# Sheet1.net
KiCad netlist of a schematic drawn in Altium Designer
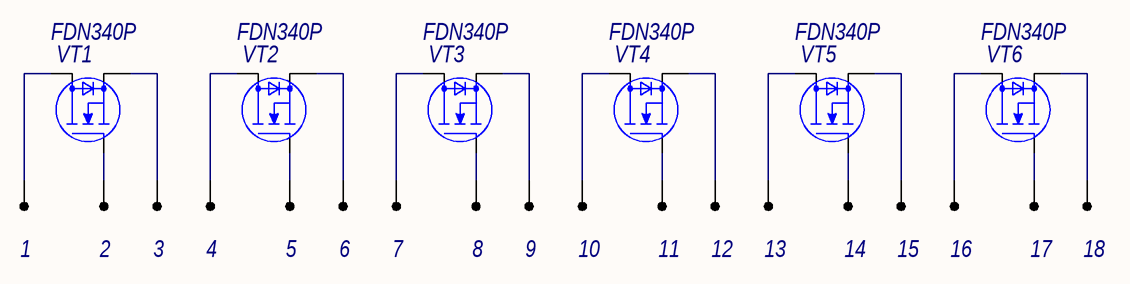
[diagram p0: Sheet1.SchDoc]

(export (version "E")
  (design (tool "Eeschema 10.0.6"))
  (components
    (comp (ref "1")
      (value "~")
      (footprint "WIRE_SOLDER_POINT2.1_0.5")
      (description "Контакт")
      (libsource (lib "headers") (part "SolderPoint"))
    )
    (comp (ref "2")
      (value "~")
      (footprint "WIRE_SOLDER_POINT2.1_0.5")
      (description "Контакт")
      (libsource (lib "headers") (part "SolderPoint"))
    )
    (comp (ref "3")
      (value "~")
      (footprint "WIRE_SOLDER_POINT2.1_0.5")
      (description "Контакт")
      (libsource (lib "headers") (part "SolderPoint"))
    )
    (comp (ref "4")
      (value "~")
      (footprint "WIRE_SOLDER_POINT2.1_0.5")
      (description "Контакт")
      (libsource (lib "headers") (part "SolderPoint"))
    )
    (comp (ref "5")
      (value "~")
      (footprint "WIRE_SOLDER_POINT2.1_0.5")
      (description "Контакт")
      (libsource (lib "headers") (part "SolderPoint"))
    )
    (comp (ref "6")
      (value "~")
      (footprint "WIRE_SOLDER_POINT2.1_0.5")
      (description "Контакт")
      (libsource (lib "headers") (part "SolderPoint"))
    )
    (comp (ref "7")
      (value "~")
      (footprint "WIRE_SOLDER_POINT2.1_0.5")
      (description "Контакт")
      (libsource (lib "headers") (part "SolderPoint"))
    )
    (comp (ref "8")
      (value "~")
      (footprint "WIRE_SOLDER_POINT2.1_0.5")
      (description "Контакт")
      (libsource (lib "headers") (part "SolderPoint"))
    )
    (comp (ref "9")
      (value "~")
      (footprint "WIRE_SOLDER_POINT2.1_0.5")
      (description "Контакт")
      (libsource (lib "headers") (part "SolderPoint"))
    )
    (comp (ref "10")
      (value "~")
      (footprint "WIRE_SOLDER_POINT2.1_0.5")
      (description "Контакт")
      (libsource (lib "headers") (part "SolderPoint"))
    )
    (comp (ref "11")
      (value "~")
      (footprint "WIRE_SOLDER_POINT2.1_0.5")
      (description "Контакт")
      (libsource (lib "headers") (part "SolderPoint"))
    )
    (comp (ref "12")
      (value "~")
      (footprint "WIRE_SOLDER_POINT2.1_0.5")
      (description "Контакт")
      (libsource (lib "headers") (part "SolderPoint"))
    )
    (comp (ref "13")
      (value "~")
      (footprint "WIRE_SOLDER_POINT2.1_0.5")
      (description "Контакт")
      (libsource (lib "headers") (part "SolderPoint"))
    )
    (comp (ref "14")
      (value "~")
      (footprint "WIRE_SOLDER_POINT2.1_0.5")
      (description "Контакт")
      (libsource (lib "headers") (part "SolderPoint"))
    )
    (comp (ref "15")
      (value "~")
      (footprint "WIRE_SOLDER_POINT2.1_0.5")
      (description "Контакт")
      (libsource (lib "headers") (part "SolderPoint"))
    )
    (comp (ref "16")
      (value "~")
      (footprint "WIRE_SOLDER_POINT2.1_0.5")
      (description "Контакт")
      (libsource (lib "headers") (part "SolderPoint"))
    )
    (comp (ref "17")
      (value "~")
      (footprint "WIRE_SOLDER_POINT2.1_0.5")
      (description "Контакт")
      (libsource (lib "headers") (part "SolderPoint"))
    )
    (comp (ref "18")
      (value "~")
      (footprint "WIRE_SOLDER_POINT2.1_0.5")
      (description "Контакт")
      (libsource (lib "headers") (part "SolderPoint"))
    )
    (comp (ref "VT1")
      (value "FDN340P")
      (footprint "SOT23")
      (libsource (lib "MZBT_SchLibrary") (part "FDN340P"))
    )
    (comp (ref "VT2")
      (value "FDN340P")
      (footprint "SOT23")
      (libsource (lib "MZBT_SchLibrary") (part "FDN340P"))
    )
    (comp (ref "VT3")
      (value "FDN340P")
      (footprint "SOT23")
      (libsource (lib "MZBT_SchLibrary") (part "FDN340P"))
    )
    (comp (ref "VT4")
      (value "FDN340P")
      (footprint "SOT23")
      (libsource (lib "MZBT_SchLibrary") (part "FDN340P"))
    )
    (comp (ref "VT5")
      (value "FDN340P")
      (footprint "SOT23")
      (libsource (lib "MZBT_SchLibrary") (part "FDN340P"))
    )
    (comp (ref "VT6")
      (value "FDN340P")
      (footprint "SOT23")
      (libsource (lib "MZBT_SchLibrary") (part "FDN340P"))
    )
  )
  (nets
    (net (code "1") (name "Net-(VT1-D)") (class "Default")
      (node (ref "1") (pin "1") (pinfunction "1_1") (pintype "passive"))
      (node (ref "VT1") (pin "3") (pinfunction "D_3") (pintype "passive"))
    )
    (net (code "2") (name "Net-(VT1-G)") (class "Default")
      (node (ref "2") (pin "1") (pinfunction "1_1") (pintype "passive"))
      (node (ref "VT1") (pin "1") (pinfunction "G_1") (pintype "passive"))
    )
    (net (code "3") (name "Net-(VT1-S)") (class "Default")
      (node (ref "3") (pin "1") (pinfunction "1_1") (pintype "passive"))
      (node (ref "VT1") (pin "2") (pinfunction "S_2") (pintype "passive"))
    )
    (net (code "4") (name "Net-(VT2-D)") (class "Default")
      (node (ref "4") (pin "1") (pinfunction "1_1") (pintype "passive"))
      (node (ref "VT2") (pin "3") (pinfunction "D_3") (pintype "passive"))
    )
    (net (code "5") (name "Net-(VT2-G)") (class "Default")
      (node (ref "5") (pin "1") (pinfunction "1_1") (pintype "passive"))
      (node (ref "VT2") (pin "1") (pinfunction "G_1") (pintype "passive"))
    )
    (net (code "6") (name "Net-(VT2-S)") (class "Default")
      (node (ref "6") (pin "1") (pinfunction "1_1") (pintype "passive"))
      (node (ref "VT2") (pin "2") (pinfunction "S_2") (pintype "passive"))
    )
    (net (code "7") (name "Net-(VT3-D)") (class "Default")
      (node (ref "7") (pin "1") (pinfunction "1_1") (pintype "passive"))
      (node (ref "VT3") (pin "3") (pinfunction "D_3") (pintype "passive"))
    )
    (net (code "8") (name "Net-(VT3-G)") (class "Default")
      (node (ref "8") (pin "1") (pinfunction "1_1") (pintype "passive"))
      (node (ref "VT3") (pin "1") (pinfunction "G_1") (pintype "passive"))
    )
    (net (code "9") (name "Net-(VT3-S)") (class "Default")
      (node (ref "9") (pin "1") (pinfunction "1_1") (pintype "passive"))
      (node (ref "VT3") (pin "2") (pinfunction "S_2") (pintype "passive"))
    )
    (net (code "10") (name "Net-(VT4-D)") (class "Default")
      (node (ref "10") (pin "1") (pinfunction "1_1") (pintype "passive"))
      (node (ref "VT4") (pin "3") (pinfunction "D_3") (pintype "passive"))
    )
    (net (code "11") (name "Net-(VT4-G)") (class "Default")
      (node (ref "11") (pin "1") (pinfunction "1_1") (pintype "passive"))
      (node (ref "VT4") (pin "1") (pinfunction "G_1") (pintype "passive"))
    )
    (net (code "12") (name "Net-(VT4-S)") (class "Default")
      (node (ref "12") (pin "1") (pinfunction "1_1") (pintype "passive"))
      (node (ref "VT4") (pin "2") (pinfunction "S_2") (pintype "passive"))
    )
    (net (code "13") (name "Net-(VT5-D)") (class "Default")
      (node (ref "13") (pin "1") (pinfunction "1_1") (pintype "passive"))
      (node (ref "VT5") (pin "3") (pinfunction "D_3") (pintype "passive"))
    )
    (net (code "14") (name "Net-(VT5-G)") (class "Default")
      (node (ref "14") (pin "1") (pinfunction "1_1") (pintype "passive"))
      (node (ref "VT5") (pin "1") (pinfunction "G_1") (pintype "passive"))
    )
    (net (code "15") (name "Net-(VT5-S)") (class "Default")
      (node (ref "15") (pin "1") (pinfunction "1_1") (pintype "passive"))
      (node (ref "VT5") (pin "2") (pinfunction "S_2") (pintype "passive"))
    )
    (net (code "16") (name "Net-(VT6-D)") (class "Default")
      (node (ref "16") (pin "1") (pinfunction "1_1") (pintype "passive"))
      (node (ref "VT6") (pin "3") (pinfunction "D_3") (pintype "passive"))
    )
    (net (code "17") (name "Net-(VT6-G)") (class "Default")
      (node (ref "17") (pin "1") (pinfunction "1_1") (pintype "passive"))
      (node (ref "VT6") (pin "1") (pinfunction "G_1") (pintype "passive"))
    )
    (net (code "18") (name "Net-(VT6-S)") (class "Default")
      (node (ref "18") (pin "1") (pinfunction "1_1") (pintype "passive"))
      (node (ref "VT6") (pin "2") (pinfunction "S_2") (pintype "passive"))
    )
  )
)
